# md_ver10_5.net
KiCad netlist of a schematic drawn in EAGLE
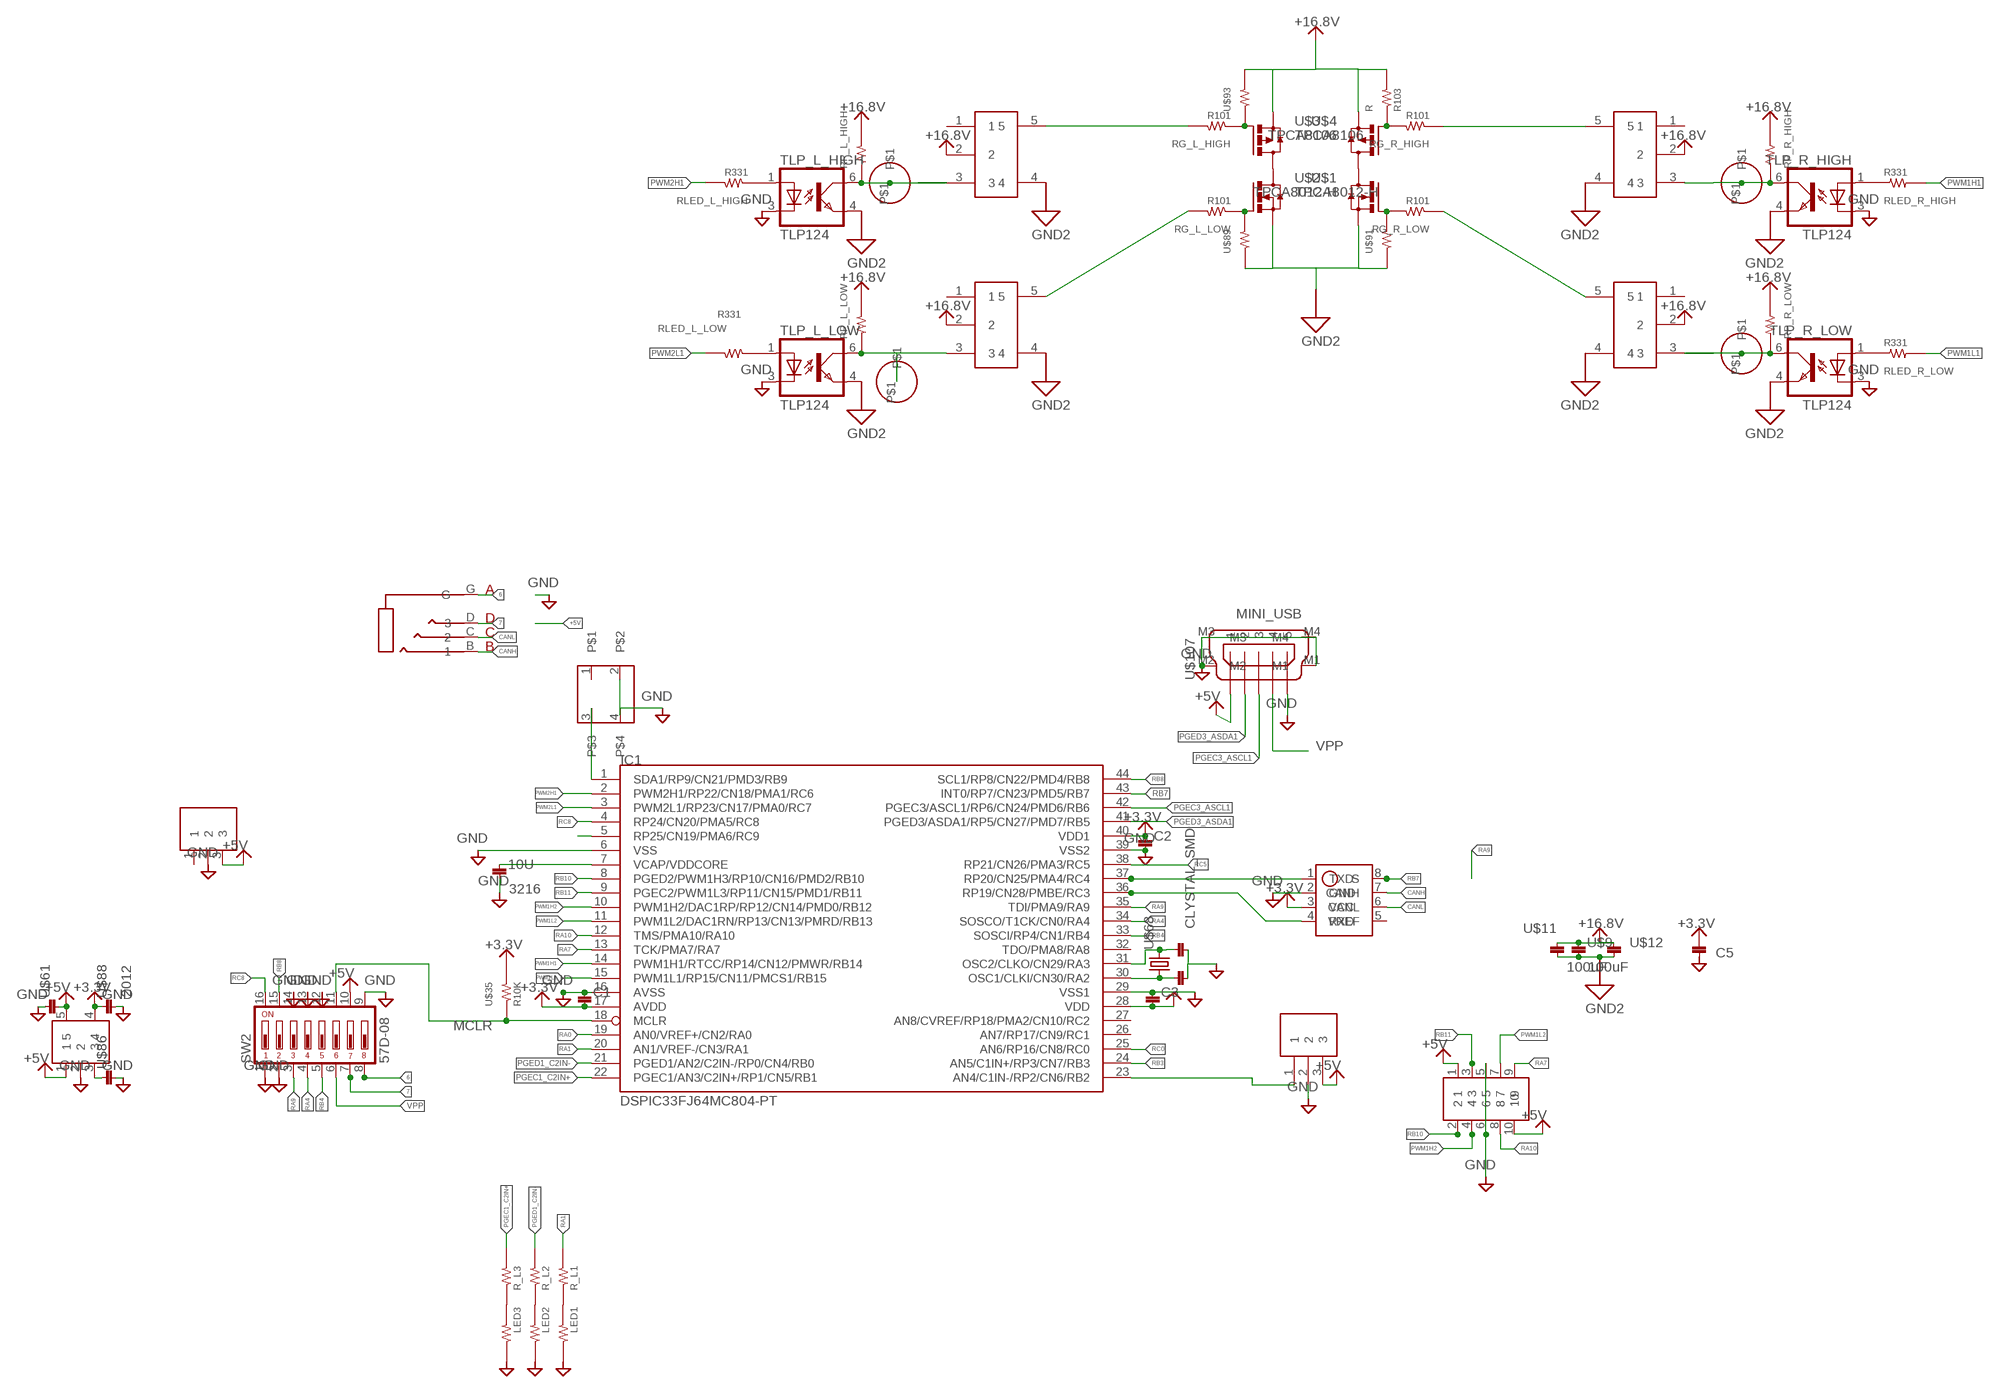
[diagram p0: schematic, sheet 1]

(export (version "E")
  (design (tool "Eeschema 10.0.6"))
  (components
    (comp (ref "10U")
      (value "3216")
      (footprint "eagle-import:3216")
      (libsource (lib "eagle-import") (part "3216"))
    )
    (comp (ref "C")
      (value "C5")
      (footprint "eagle-import:1608")
      (libsource (lib "eagle-import") (part "1608"))
    )
    (comp (ref "C1")
      (value "1608")
      (footprint "eagle-import:1608")
      (libsource (lib "eagle-import") (part "1608"))
    )
    (comp (ref "C2")
      (value "1608")
      (footprint "eagle-import:1608")
      (libsource (lib "eagle-import") (part "1608"))
    )
    (comp (ref "C3")
      (value "1608")
      (footprint "eagle-import:1608")
      (libsource (lib "eagle-import") (part "1608"))
    )
    (comp (ref "IC1")
      (value "DSPIC33FJ64MC804-PT")
      (footprint "eagle-import:TQFP44")
      (libsource (lib "eagle-import") (part "DSPIC33FJ64MC804-PT"))
    )
    (comp (ref "IC2")
      (value "TAR5SB")
      (footprint "eagle-import:SSOP5-P-0.95")
      (libsource (lib "eagle-import") (part "TAR5SB"))
    )
    (comp (ref "IC3")
      (value "ＰＬ－ＩＲＭ")
      (footprint "eagle-import:ＰＬ－ＩＲＭ")
      (libsource (lib "eagle-import") (part "ＰＬ－ＩＲＭ"))
    )
    (comp (ref "IC4")
      (value "SN65HVD1050")
      (footprint "eagle-import:SOIC8")
      (libsource (lib "eagle-import") (part "SN65HVD1050"))
    )
    (comp (ref "IC5")
      (value "Ｒ－７８Ｅ５．０")
      (footprint "eagle-import:Ｒ－７８Ｅ５．０")
      (libsource (lib "eagle-import") (part "Ｒ－７８Ｅ５．０"))
    )
    (comp (ref "IC_L_HIGH")
      (value "MCP1415")
      (footprint "eagle-import:SOT23-5L")
      (libsource (lib "eagle-import") (part "MCP1415"))
    )
    (comp (ref "IC_L_LOW")
      (value "MCP1415")
      (footprint "eagle-import:SOT23-5L")
      (libsource (lib "eagle-import") (part "MCP1415"))
    )
    (comp (ref "IC_R_HIGH")
      (value "MCP1415")
      (footprint "eagle-import:SOT23-5L")
      (libsource (lib "eagle-import") (part "MCP1415"))
    )
    (comp (ref "IC_R_LOW")
      (value "MCP1415")
      (footprint "eagle-import:SOT23-5L")
      (libsource (lib "eagle-import") (part "MCP1415"))
    )
    (comp (ref "R")
      (value "R103")
      (footprint "eagle-import:1608")
      (libsource (lib "eagle-import") (part "RESISTOR__SMD"))
    )
    (comp (ref "RG_L_HIGH")
      (value "R101")
      (footprint "eagle-import:1608")
      (libsource (lib "eagle-import") (part "RESISTOR__SMD"))
    )
    (comp (ref "RG_L_LOW")
      (value "R101")
      (footprint "eagle-import:1608")
      (libsource (lib "eagle-import") (part "RESISTOR__SMD"))
    )
    (comp (ref "RG_R_HIGH")
      (value "R101")
      (footprint "eagle-import:1608")
      (libsource (lib "eagle-import") (part "RESISTOR__SMD"))
    )
    (comp (ref "RG_R_LOW")
      (value "R101")
      (footprint "eagle-import:1608")
      (libsource (lib "eagle-import") (part "RESISTOR__SMD"))
    )
    (comp (ref "RLED_L_HIGH")
      (value "R331")
      (footprint "eagle-import:1608")
      (libsource (lib "eagle-import") (part "RESISTOR__SMD"))
    )
    (comp (ref "RLED_L_LOW")
      (value "R331")
      (footprint "eagle-import:1608")
      (libsource (lib "eagle-import") (part "RESISTOR__SMD"))
    )
    (comp (ref "RLED_R_HIGH")
      (value "R331")
      (footprint "eagle-import:1608")
      (libsource (lib "eagle-import") (part "RESISTOR__SMD"))
    )
    (comp (ref "RLED_R_LOW")
      (value "R331")
      (footprint "eagle-import:1608")
      (libsource (lib "eagle-import") (part "RESISTOR__SMD"))
    )
    (comp (ref "RP_L_HIGH")
      (value "RESISTOR__SMD")
      (footprint "eagle-import:1608")
      (libsource (lib "eagle-import") (part "RESISTOR__SMD"))
    )
    (comp (ref "RP_L_LOW")
      (value "RESISTOR__SMD")
      (footprint "eagle-import:1608")
      (libsource (lib "eagle-import") (part "RESISTOR__SMD"))
    )
    (comp (ref "RP_R_HIGH")
      (value "RESISTOR__SMD")
      (footprint "eagle-import:1608")
      (libsource (lib "eagle-import") (part "RESISTOR__SMD"))
    )
    (comp (ref "RP_R_LOW")
      (value "RESISTOR__SMD")
      (footprint "eagle-import:1608")
      (libsource (lib "eagle-import") (part "RESISTOR__SMD"))
    )
    (comp (ref "SW1")
      (value "TACT")
      (footprint "eagle-import:TL1105")
      (libsource (lib "eagle-import") (part "TACT"))
    )
    (comp (ref "SW2")
      (value "57D-08")
      (footprint "eagle-import:57D")
      (libsource (lib "eagle-import") (part "57D-08"))
    )
    (comp (ref "TLP_L_HIGH")
      (value "TLP124")
      (footprint "eagle-import:11−4C1")
      (libsource (lib "eagle-import") (part "TLP124"))
    )
    (comp (ref "TLP_L_LOW")
      (value "TLP124")
      (footprint "eagle-import:11−4C1")
      (libsource (lib "eagle-import") (part "TLP124"))
    )
    (comp (ref "TLP_R_HIGH")
      (value "TLP124")
      (footprint "eagle-import:11−4C1")
      (libsource (lib "eagle-import") (part "TLP124"))
    )
    (comp (ref "TLP_R_LOW")
      (value "TLP124")
      (footprint "eagle-import:11−4C1")
      (libsource (lib "eagle-import") (part "TLP124"))
    )
    (comp (ref "U$1")
      (value "TPCA8012-H")
      (footprint "eagle-import:2-5Q1A")
      (libsource (lib "eagle-import") (part "TPCA8012-H"))
    )
    (comp (ref "U$2")
      (value "TPCA8012-H")
      (footprint "eagle-import:2-5Q1A")
      (libsource (lib "eagle-import") (part "TPCA8012-H"))
    )
    (comp (ref "U$3")
      (value "TPCA8106")
      (footprint "eagle-import:2-5Q1A")
      (libsource (lib "eagle-import") (part "TPCA8106"))
    )
    (comp (ref "U$4")
      (value "TPCA8106")
      (footprint "eagle-import:2-5Q1A")
      (libsource (lib "eagle-import") (part "TPCA8106"))
    )
    (comp (ref "U$7")
      (value "20pF")
      (footprint "eagle-import:1608")
      (libsource (lib "eagle-import") (part "1608"))
    )
    (comp (ref "U$8")
      (value "20pF")
      (footprint "eagle-import:1608")
      (libsource (lib "eagle-import") (part "1608"))
    )
    (comp (ref "U$9")
      (value "100uF")
      (footprint "eagle-import:3225")
      (libsource (lib "eagle-import") (part "3225"))
    )
    (comp (ref "U$11")
      (value "100uF")
      (footprint "eagle-import:3225")
      (libsource (lib "eagle-import") (part "3225"))
    )
    (comp (ref "U$12")
      (value "3225")
      (footprint "eagle-import:3225")
      (libsource (lib "eagle-import") (part "3225"))
    )
    (comp (ref "U$15")
      (value "PIN_HEADER_52")
      (footprint "eagle-import:PIN_HEADER_5_2")
      (libsource (lib "eagle-import") (part "PIN_HEADER_52"))
    )
    (comp (ref "U$35")
      (value "R10K")
      (footprint "eagle-import:1608")
      (libsource (lib "eagle-import") (part "RESISTOR__SMD"))
    )
    (comp (ref "U$61")
      (value "1608")
      (footprint "eagle-import:1608")
      (libsource (lib "eagle-import") (part "1608"))
    )
    (comp (ref "U$64")
      (value "AUDIO4")
      (footprint "eagle-import:AUDIO4_MJ")
      (libsource (lib "eagle-import") (part "AUDIO4"))
    )
    (comp (ref "U$68")
      (value "CLYSTAL_SMD")
      (footprint "eagle-import:CRYSTAL_SMD")
      (libsource (lib "eagle-import") (part "CLYSTAL_SMD"))
    )
    (comp (ref "U$72")
      (value "R_L3")
      (footprint "eagle-import:1608")
      (libsource (lib "eagle-import") (part "RESISTOR__SMD"))
    )
    (comp (ref "U$74")
      (value "LED3")
      (footprint "eagle-import:1608")
      (libsource (lib "eagle-import") (part "RESISTOR__SMD"))
    )
    (comp (ref "U$75")
      (value "R_L2")
      (footprint "eagle-import:1608")
      (libsource (lib "eagle-import") (part "RESISTOR__SMD"))
    )
    (comp (ref "U$76")
      (value "LED2")
      (footprint "eagle-import:1608")
      (libsource (lib "eagle-import") (part "RESISTOR__SMD"))
    )
    (comp (ref "U$77")
      (value "R_L1")
      (footprint "eagle-import:1608")
      (libsource (lib "eagle-import") (part "RESISTOR__SMD"))
    )
    (comp (ref "U$78")
      (value "LED1")
      (footprint "eagle-import:1608")
      (libsource (lib "eagle-import") (part "RESISTOR__SMD"))
    )
    (comp (ref "U$86")
      (value "1608")
      (footprint "eagle-import:1608")
      (libsource (lib "eagle-import") (part "1608"))
    )
    (comp (ref "U$88")
      (value "2012")
      (footprint "eagle-import:2012")
      (libsource (lib "eagle-import") (part "2012"))
    )
    (comp (ref "U$89")
      (value "RESISTOR__SMD")
      (footprint "eagle-import:1608")
      (libsource (lib "eagle-import") (part "RESISTOR__SMD"))
    )
    (comp (ref "U$91")
      (value "RESISTOR__SMD")
      (footprint "eagle-import:1608")
      (libsource (lib "eagle-import") (part "RESISTOR__SMD"))
    )
    (comp (ref "U$93")
      (value "RESISTOR__SMD")
      (footprint "eagle-import:1608")
      (libsource (lib "eagle-import") (part "RESISTOR__SMD"))
    )
    (comp (ref "U$103")
      (value "PAD1_4MM")
      (footprint "eagle-import:PAD1_4MM")
      (libsource (lib "eagle-import") (part "PAD1_4MM"))
    )
    (comp (ref "U$104")
      (value "PAD1_4MM")
      (footprint "eagle-import:PAD1_4MM")
      (libsource (lib "eagle-import") (part "PAD1_4MM"))
    )
    (comp (ref "U$105")
      (value "PAD1_4MM")
      (footprint "eagle-import:PAD1_4MM")
      (libsource (lib "eagle-import") (part "PAD1_4MM"))
    )
    (comp (ref "U$106")
      (value "PAD1_4MM")
      (footprint "eagle-import:PAD1_4MM")
      (libsource (lib "eagle-import") (part "PAD1_4MM"))
    )
    (comp (ref "U$107")
      (value "MINI_USB")
      (footprint "eagle-import:MINI_USB")
      (libsource (lib "eagle-import") (part "MINI_USB"))
    )
  )
  (nets
    (net (code "1") (name "+3.3V") (class "Default")
      (node (ref "C") (pin "P$1") (pinfunction "1_P$1") (pintype "passive"))
      (node (ref "C1") (pin "P$2") (pinfunction "2_P$2") (pintype "passive"))
      (node (ref "C2") (pin "P$1") (pinfunction "1_P$1") (pintype "passive"))
      (node (ref "C3") (pin "P$2") (pinfunction "2_P$2") (pintype "passive"))
      (node (ref "IC1") (pin "17") (pinfunction "AVDD_17") (pintype "power_in"))
      (node (ref "IC1") (pin "28") (pinfunction "VDD_28") (pintype "power_in"))
      (node (ref "IC1") (pin "40") (pinfunction "VDD1_40") (pintype "power_in"))
      (node (ref "IC2") (pin "4") (pinfunction "4_4") (pintype "bidirectional"))
      (node (ref "IC4") (pin "3") (pinfunction "VCC_3") (pintype "bidirectional"))
      (node (ref "U$35") (pin "2") (pinfunction "P$2_2") (pintype "passive"))
      (node (ref "U$88") (pin "1") (pinfunction "1_1") (pintype "passive"))
    )
    (net (code "2") (name "+5V") (class "Default")
      (node (ref "IC2") (pin "1") (pinfunction "1_1") (pintype "bidirectional"))
      (node (ref "IC2") (pin "5") (pinfunction "5_5") (pintype "bidirectional"))
      (node (ref "IC3") (pin "3") (pinfunction "3_3") (pintype "bidirectional"))
      (node (ref "IC5") (pin "3") (pinfunction "3_3") (pintype "bidirectional"))
      (node (ref "SW2") (pin "10") (pinfunction "10_10") (pintype "passive"))
      (node (ref "U$107") (pin "1") (pinfunction "1_1") (pintype "input"))
      (node (ref "U$15") (pin "1") (pinfunction "1_1") (pintype "bidirectional"))
      (node (ref "U$15") (pin "10") (pinfunction "10_10") (pintype "bidirectional"))
      (node (ref "U$61") (pin "P$2") (pinfunction "2_P$2") (pintype "passive"))
    )
    (net (code "3") (name "+16.8V") (class "Default")
      (node (ref "IC_L_HIGH") (pin "2") (pinfunction "2_2") (pintype "bidirectional"))
      (node (ref "IC_L_LOW") (pin "2") (pinfunction "2_2") (pintype "bidirectional"))
      (node (ref "IC_R_HIGH") (pin "2") (pinfunction "2_2") (pintype "bidirectional"))
      (node (ref "IC_R_LOW") (pin "2") (pinfunction "2_2") (pintype "bidirectional"))
      (node (ref "R") (pin "2") (pinfunction "P$2_2") (pintype "passive"))
      (node (ref "RP_L_HIGH") (pin "2") (pinfunction "P$2_2") (pintype "passive"))
      (node (ref "RP_L_LOW") (pin "2") (pinfunction "P$2_2") (pintype "passive"))
      (node (ref "RP_R_HIGH") (pin "2") (pinfunction "P$2_2") (pintype "passive"))
      (node (ref "RP_R_LOW") (pin "2") (pinfunction "P$2_2") (pintype "passive"))
      (node (ref "U$11") (pin "P$1") (pinfunction "1_P$1") (pintype "passive"))
      (node (ref "U$12") (pin "P$1") (pinfunction "1_P$1") (pintype "passive"))
      (node (ref "U$3") (pin "1") (pinfunction "S_1") (pintype "passive"))
      (node (ref "U$3") (pin "2") (pinfunction "S_2") (pintype "passive"))
      (node (ref "U$3") (pin "3") (pinfunction "S_3") (pintype "passive"))
      (node (ref "U$4") (pin "1") (pinfunction "S_1") (pintype "passive"))
      (node (ref "U$4") (pin "2") (pinfunction "S_2") (pintype "passive"))
      (node (ref "U$4") (pin "3") (pinfunction "S_3") (pintype "passive"))
      (node (ref "U$9") (pin "P$1") (pinfunction "1_P$1") (pintype "passive"))
      (node (ref "U$93") (pin "2") (pinfunction "P$2_2") (pintype "passive"))
    )
    (net (code "4") (name "/MCLR") (class "Default")
      (node (ref "IC1") (pin "18") (pinfunction "MCLR_18") (pintype "input"))
      (node (ref "SW2") (pin "11") (pinfunction "11_11") (pintype "passive"))
      (node (ref "U$35") (pin "1") (pinfunction "P$1_1") (pintype "passive"))
    )
    (net (code "5") (name "6") (class "Default")
      (node (ref "SW2") (pin "8") (pinfunction "8_8") (pintype "passive"))
      (node (ref "U$64") (pin "G") (pinfunction "G_G") (pintype "bidirectional"))
    )
    (net (code "6") (name "7") (class "Default")
      (node (ref "SW2") (pin "7") (pinfunction "7_7") (pintype "passive"))
      (node (ref "U$64") (pin "D") (pinfunction "3_D") (pintype "bidirectional"))
    )
    (net (code "7") (name "CANH") (class "Default")
      (node (ref "IC4") (pin "7") (pinfunction "CANH_7") (pintype "bidirectional"))
      (node (ref "U$64") (pin "B") (pinfunction "1_B") (pintype "bidirectional"))
    )
    (net (code "8") (name "CANL") (class "Default")
      (node (ref "IC4") (pin "6") (pinfunction "CANL_6") (pintype "bidirectional"))
      (node (ref "U$64") (pin "C") (pinfunction "2_C") (pintype "bidirectional"))
    )
    (net (code "9") (name "GND") (class "Default")
      (node (ref "10U") (pin "P$2") (pinfunction "2_P$2") (pintype "passive"))
      (node (ref "C") (pin "P$2") (pinfunction "2_P$2") (pintype "passive"))
      (node (ref "C1") (pin "P$1") (pinfunction "1_P$1") (pintype "passive"))
      (node (ref "C2") (pin "P$2") (pinfunction "2_P$2") (pintype "passive"))
      (node (ref "C3") (pin "P$1") (pinfunction "1_P$1") (pintype "passive"))
      (node (ref "IC1") (pin "16") (pinfunction "AVSS_16") (pintype "power_in"))
      (node (ref "IC1") (pin "29") (pinfunction "VSS1_29") (pintype "power_in"))
      (node (ref "IC1") (pin "39") (pinfunction "VSS2_39") (pintype "power_in"))
      (node (ref "IC1") (pin "6") (pinfunction "VSS_6") (pintype "power_in"))
      (node (ref "IC2") (pin "2") (pinfunction "2_2") (pintype "bidirectional"))
      (node (ref "IC3") (pin "2") (pinfunction "2_2") (pintype "bidirectional"))
      (node (ref "IC4") (pin "2") (pinfunction "GND_2") (pintype "bidirectional"))
      (node (ref "IC5") (pin "2") (pinfunction "2_2") (pintype "bidirectional"))
      (node (ref "SW1") (pin "2") (pinfunction "P$2_2") (pintype "bidirectional"))
      (node (ref "SW1") (pin "4") (pinfunction "P$4_4") (pintype "bidirectional"))
      (node (ref "SW2") (pin "1") (pinfunction "1_1") (pintype "passive"))
      (node (ref "SW2") (pin "12") (pinfunction "12_12") (pintype "passive"))
      (node (ref "SW2") (pin "13") (pinfunction "13_13") (pintype "passive"))
      (node (ref "SW2") (pin "14") (pinfunction "14_14") (pintype "passive"))
      (node (ref "SW2") (pin "2") (pinfunction "2_2") (pintype "passive"))
      (node (ref "SW2") (pin "9") (pinfunction "9_9") (pintype "passive"))
      (node (ref "TLP_L_HIGH") (pin "3") (pinfunction "C_3") (pintype "passive"))
      (node (ref "TLP_L_LOW") (pin "3") (pinfunction "C_3") (pintype "passive"))
      (node (ref "TLP_R_HIGH") (pin "3") (pinfunction "C_3") (pintype "passive"))
      (node (ref "TLP_R_LOW") (pin "3") (pinfunction "C_3") (pintype "passive"))
      (node (ref "U$107") (pin "5") (pinfunction "5_5") (pintype "input"))
      (node (ref "U$107") (pin "M1") (pinfunction "M1_M1") (pintype "bidirectional"))
      (node (ref "U$107") (pin "M2") (pinfunction "M2_M2") (pintype "bidirectional"))
      (node (ref "U$107") (pin "M3") (pinfunction "M3_M3") (pintype "bidirectional"))
      (node (ref "U$107") (pin "M4") (pinfunction "M4_M4") (pintype "bidirectional"))
      (node (ref "U$15") (pin "5") (pinfunction "5_5") (pintype "bidirectional"))
      (node (ref "U$15") (pin "6") (pinfunction "6_6") (pintype "bidirectional"))
      (node (ref "U$61") (pin "P$1") (pinfunction "1_P$1") (pintype "passive"))
      (node (ref "U$7") (pin "P$2") (pinfunction "2_P$2") (pintype "passive"))
      (node (ref "U$74") (pin "1") (pinfunction "P$1_1") (pintype "passive"))
      (node (ref "U$76") (pin "1") (pinfunction "P$1_1") (pintype "passive"))
      (node (ref "U$78") (pin "1") (pinfunction "P$1_1") (pintype "passive"))
      (node (ref "U$8") (pin "P$2") (pinfunction "2_P$2") (pintype "passive"))
      (node (ref "U$86") (pin "P$2") (pinfunction "2_P$2") (pintype "passive"))
      (node (ref "U$88") (pin "2") (pinfunction "2_2") (pintype "passive"))
    )
    (net (code "10") (name "GND2") (class "Default")
      (node (ref "IC_L_HIGH") (pin "4") (pinfunction "4_4") (pintype "bidirectional"))
      (node (ref "IC_L_LOW") (pin "4") (pinfunction "4_4") (pintype "bidirectional"))
      (node (ref "IC_R_HIGH") (pin "4") (pinfunction "4_4") (pintype "bidirectional"))
      (node (ref "IC_R_LOW") (pin "4") (pinfunction "4_4") (pintype "bidirectional"))
      (node (ref "TLP_L_HIGH") (pin "4") (pinfunction "EMIT_4") (pintype "passive"))
      (node (ref "TLP_L_LOW") (pin "4") (pinfunction "EMIT_4") (pintype "passive"))
      (node (ref "TLP_R_HIGH") (pin "4") (pinfunction "EMIT_4") (pintype "passive"))
      (node (ref "TLP_R_LOW") (pin "4") (pinfunction "EMIT_4") (pintype "passive"))
      (node (ref "U$1") (pin "1") (pinfunction "S_1") (pintype "passive"))
      (node (ref "U$1") (pin "2") (pinfunction "S_2") (pintype "passive"))
      (node (ref "U$1") (pin "3") (pinfunction "S_3") (pintype "passive"))
      (node (ref "U$11") (pin "P$2") (pinfunction "2_P$2") (pintype "passive"))
      (node (ref "U$12") (pin "P$2") (pinfunction "2_P$2") (pintype "passive"))
      (node (ref "U$2") (pin "1") (pinfunction "S_1") (pintype "passive"))
      (node (ref "U$2") (pin "2") (pinfunction "S_2") (pintype "passive"))
      (node (ref "U$2") (pin "3") (pinfunction "S_3") (pintype "passive"))
      (node (ref "U$89") (pin "1") (pinfunction "P$1_1") (pintype "passive"))
      (node (ref "U$9") (pin "P$2") (pinfunction "2_P$2") (pintype "passive"))
      (node (ref "U$91") (pin "1") (pinfunction "P$1_1") (pintype "passive"))
    )
    (net (code "11") (name "Net-(10U-1)") (class "Default")
      (node (ref "10U") (pin "P$1") (pinfunction "1_P$1") (pintype "passive"))
      (node (ref "IC1") (pin "7") (pinfunction "VCAP/VDDCORE_7") (pintype "power_in"))
    )
    (net (code "12") (name "Net-(IC1-AN4{slash}C1IN-{slash}RP2{slash}CN6{slash}RB2)") (class "Default")
      (node (ref "IC1") (pin "23") (pinfunction "AN4/C1IN-/RP2/CN6/RB2_23") (pintype "bidirectional"))
      (node (ref "IC3") (pin "1") (pinfunction "1_1") (pintype "bidirectional"))
    )
    (net (code "13") (name "Net-(IC1-OSC1{slash}CLKI{slash}CN30{slash}RA2)") (class "Default")
      (node (ref "IC1") (pin "30") (pinfunction "OSC1/CLKI/CN30/RA2_30") (pintype "bidirectional"))
      (node (ref "U$68") (pin "1") (pinfunction "1_1") (pintype "passive"))
      (node (ref "U$7") (pin "P$1") (pinfunction "1_P$1") (pintype "passive"))
    )
    (net (code "14") (name "Net-(IC1-OSC2{slash}CLKO{slash}CN29{slash}RA3)") (class "Default")
      (node (ref "IC1") (pin "31") (pinfunction "OSC2/CLKO/CN29/RA3_31") (pintype "bidirectional"))
      (node (ref "U$68") (pin "2") (pinfunction "2_2") (pintype "passive"))
      (node (ref "U$8") (pin "P$1") (pinfunction "1_P$1") (pintype "passive"))
    )
    (net (code "15") (name "Net-(IC1-RP19{slash}CN28{slash}PMBE{slash}RC3)") (class "Default")
      (node (ref "IC1") (pin "36") (pinfunction "RP19/CN28/PMBE/RC3_36") (pintype "bidirectional"))
      (node (ref "IC4") (pin "4") (pinfunction "RXD_4") (pintype "bidirectional"))
    )
    (net (code "16") (name "Net-(IC1-RP20{slash}CN25{slash}PMA4{slash}RC4)") (class "Default")
      (node (ref "IC1") (pin "37") (pinfunction "RP20/CN25/PMA4/RC4_37") (pintype "bidirectional"))
      (node (ref "IC4") (pin "1") (pinfunction "TXD_1") (pintype "bidirectional"))
    )
    (net (code "17") (name "Net-(IC1-SDA1{slash}RP9{slash}CN21{slash}PMD3{slash}RB9)") (class "Default")
      (node (ref "IC1") (pin "1") (pinfunction "SDA1/RP9/CN21/PMD3/RB9_1") (pintype "bidirectional"))
      (node (ref "SW1") (pin "3") (pinfunction "P$3_3") (pintype "bidirectional"))
    )
    (net (code "18") (name "Net-(R-P$1)") (class "Default")
      (node (ref "R") (pin "1") (pinfunction "P$1_1") (pintype "passive"))
      (node (ref "RG_R_HIGH") (pin "2") (pinfunction "P$2_2") (pintype "passive"))
      (node (ref "U$4") (pin "4") (pinfunction "G_4") (pintype "passive"))
    )
    (net (code "19") (name "Net-(RG_L_HIGH-P$1)") (class "Default")
      (node (ref "RG_L_HIGH") (pin "1") (pinfunction "P$1_1") (pintype "passive"))
      (node (ref "U$3") (pin "4") (pinfunction "G_4") (pintype "passive"))
      (node (ref "U$93") (pin "1") (pinfunction "P$1_1") (pintype "passive"))
    )
    (net (code "20") (name "Net-(RG_L_HIGH-P$2)") (class "Default")
      (node (ref "IC_L_HIGH") (pin "5") (pinfunction "5_5") (pintype "bidirectional"))
      (node (ref "RG_L_HIGH") (pin "2") (pinfunction "P$2_2") (pintype "passive"))
    )
    (net (code "21") (name "Net-(RG_L_LOW-P$1)") (class "Default")
      (node (ref "RG_L_LOW") (pin "1") (pinfunction "P$1_1") (pintype "passive"))
      (node (ref "U$2") (pin "4") (pinfunction "G_4") (pintype "passive"))
      (node (ref "U$89") (pin "2") (pinfunction "P$2_2") (pintype "passive"))
    )
    (net (code "22") (name "Net-(RG_L_LOW-P$2)") (class "Default")
      (node (ref "IC_L_LOW") (pin "5") (pinfunction "5_5") (pintype "bidirectional"))
      (node (ref "RG_L_LOW") (pin "2") (pinfunction "P$2_2") (pintype "passive"))
    )
    (net (code "23") (name "Net-(RG_R_HIGH-P$1)") (class "Default")
      (node (ref "IC_R_HIGH") (pin "5") (pinfunction "5_5") (pintype "bidirectional"))
      (node (ref "RG_R_HIGH") (pin "1") (pinfunction "P$1_1") (pintype "passive"))
    )
    (net (code "24") (name "Net-(RG_R_LOW-P$1)") (class "Default")
      (node (ref "IC_R_LOW") (pin "5") (pinfunction "5_5") (pintype "bidirectional"))
      (node (ref "RG_R_LOW") (pin "1") (pinfunction "P$1_1") (pintype "passive"))
    )
    (net (code "25") (name "Net-(RG_R_LOW-P$2)") (class "Default")
      (node (ref "RG_R_LOW") (pin "2") (pinfunction "P$2_2") (pintype "passive"))
      (node (ref "U$1") (pin "4") (pinfunction "G_4") (pintype "passive"))
      (node (ref "U$91") (pin "2") (pinfunction "P$2_2") (pintype "passive"))
    )
    (net (code "26") (name "Net-(RLED_L_HIGH-P$1)") (class "Default")
      (node (ref "RLED_L_HIGH") (pin "1") (pinfunction "P$1_1") (pintype "passive"))
      (node (ref "TLP_L_HIGH") (pin "1") (pinfunction "A_1") (pintype "passive"))
    )
    (net (code "27") (name "Net-(RLED_L_LOW-P$1)") (class "Default")
      (node (ref "RLED_L_LOW") (pin "1") (pinfunction "P$1_1") (pintype "passive"))
      (node (ref "TLP_L_LOW") (pin "1") (pinfunction "A_1") (pintype "passive"))
    )
    (net (code "28") (name "Net-(RLED_R_HIGH-P$1)") (class "Default")
      (node (ref "RLED_R_HIGH") (pin "1") (pinfunction "P$1_1") (pintype "passive"))
      (node (ref "TLP_R_HIGH") (pin "1") (pinfunction "A_1") (pintype "passive"))
    )
    (net (code "29") (name "Net-(RLED_R_LOW-P$1)") (class "Default")
      (node (ref "RLED_R_LOW") (pin "1") (pinfunction "P$1_1") (pintype "passive"))
      (node (ref "TLP_R_LOW") (pin "1") (pinfunction "A_1") (pintype "passive"))
    )
    (net (code "30") (name "Net-(RP_L_HIGH-P$1)") (class "Default")
      (node (ref "IC_L_HIGH") (pin "3") (pinfunction "3_3") (pintype "bidirectional"))
      (node (ref "RP_L_HIGH") (pin "1") (pinfunction "P$1_1") (pintype "passive"))
      (node (ref "TLP_L_HIGH") (pin "6") (pinfunction "COL_6") (pintype "passive"))
      (node (ref "U$103") (pin "P$1") (pinfunction "P$1_P$1") (pintype "bidirectional"))
    )
    (net (code "31") (name "Net-(RP_L_LOW-P$1)") (class "Default")
      (node (ref "IC_L_LOW") (pin "3") (pinfunction "3_3") (pintype "bidirectional"))
      (node (ref "RP_L_LOW") (pin "1") (pinfunction "P$1_1") (pintype "passive"))
      (node (ref "TLP_L_LOW") (pin "6") (pinfunction "COL_6") (pintype "passive"))
      (node (ref "U$104") (pin "P$1") (pinfunction "P$1_P$1") (pintype "bidirectional"))
    )
    (net (code "32") (name "Net-(RP_R_HIGH-P$1)") (class "Default")
      (node (ref "IC_R_HIGH") (pin "3") (pinfunction "3_3") (pintype "bidirectional"))
      (node (ref "RP_R_HIGH") (pin "1") (pinfunction "P$1_1") (pintype "passive"))
      (node (ref "TLP_R_HIGH") (pin "6") (pinfunction "COL_6") (pintype "passive"))
      (node (ref "U$105") (pin "P$1") (pinfunction "P$1_P$1") (pintype "bidirectional"))
    )
    (net (code "33") (name "Net-(RP_R_LOW-P$1)") (class "Default")
      (node (ref "IC_R_LOW") (pin "3") (pinfunction "3_3") (pintype "bidirectional"))
      (node (ref "RP_R_LOW") (pin "1") (pinfunction "P$1_1") (pintype "passive"))
      (node (ref "TLP_R_LOW") (pin "6") (pinfunction "COL_6") (pintype "passive"))
      (node (ref "U$106") (pin "P$1") (pinfunction "P$1_P$1") (pintype "bidirectional"))
    )
    (net (code "34") (name "Net-(U$1-D-Pad5)") (class "Default")
      (node (ref "U$1") (pin "5") (pinfunction "D_5") (pintype "passive"))
      (node (ref "U$1") (pin "6") (pinfunction "D_6") (pintype "passive"))
      (node (ref "U$1") (pin "7") (pinfunction "D_7") (pintype "passive"))
      (node (ref "U$1") (pin "8") (pinfunction "D_8") (pintype "passive"))
      (node (ref "U$4") (pin "5") (pinfunction "D_5") (pintype "passive"))
      (node (ref "U$4") (pin "6") (pinfunction "D_6") (pintype "passive"))
      (node (ref "U$4") (pin "7") (pinfunction "D_7") (pintype "passive"))
      (node (ref "U$4") (pin "8") (pinfunction "D_8") (pintype "passive"))
    )
    (net (code "35") (name "Net-(U$2-D-Pad5)") (class "Default")
      (node (ref "U$2") (pin "5") (pinfunction "D_5") (pintype "passive"))
      (node (ref "U$2") (pin "6") (pinfunction "D_6") (pintype "passive"))
      (node (ref "U$2") (pin "7") (pinfunction "D_7") (pintype "passive"))
      (node (ref "U$2") (pin "8") (pinfunction "D_8") (pintype "passive"))
      (node (ref "U$3") (pin "5") (pinfunction "D_5") (pintype "passive"))
      (node (ref "U$3") (pin "6") (pinfunction "D_6") (pintype "passive"))
      (node (ref "U$3") (pin "7") (pinfunction "D_7") (pintype "passive"))
      (node (ref "U$3") (pin "8") (pinfunction "D_8") (pintype "passive"))
    )
    (net (code "36") (name "Net-(U$72-P$1)") (class "Default")
      (node (ref "U$72") (pin "1") (pinfunction "P$1_1") (pintype "passive"))
      (node (ref "U$74") (pin "2") (pinfunction "P$2_2") (pintype "passive"))
    )
    (net (code "37") (name "Net-(U$75-P$1)") (class "Default")
      (node (ref "U$75") (pin "1") (pinfunction "P$1_1") (pintype "passive"))
      (node (ref "U$76") (pin "2") (pinfunction "P$2_2") (pintype "passive"))
    )
    (net (code "38") (name "Net-(U$77-P$1)") (class "Default")
      (node (ref "U$77") (pin "1") (pinfunction "P$1_1") (pintype "passive"))
      (node (ref "U$78") (pin "2") (pinfunction "P$2_2") (pintype "passive"))
    )
    (net (code "39") (name "Net-(U$86-1)") (class "Default")
      (node (ref "IC2") (pin "3") (pinfunction "3_3") (pintype "bidirectional"))
      (node (ref "U$86") (pin "P$1") (pinfunction "1_P$1") (pintype "passive"))
    )
    (net (code "40") (name "PGEC1_C2IN+") (class "Default")
      (node (ref "IC1") (pin "22") (pinfunction "PGEC1/AN3/C2IN+/RP1/CN5/RB1_22") (pintype "bidirectional"))
      (node (ref "U$72") (pin "2") (pinfunction "P$2_2") (pintype "passive"))
    )
    (net (code "41") (name "PGEC3_ASCL1") (class "Default")
      (node (ref "IC1") (pin "42") (pinfunction "PGEC3/ASCL1/RP6/CN24/PMD6/RB6_42") (pintype "bidirectional"))
      (node (ref "U$107") (pin "3") (pinfunction "3_3") (pintype "input"))
    )
    (net (code "42") (name "PGED1_C2IN-") (class "Default")
      (node (ref "IC1") (pin "21") (pinfunction "PGED1/AN2/C2IN-/RP0/CN4/RB0_21") (pintype "bidirectional"))
      (node (ref "U$75") (pin "2") (pinfunction "P$2_2") (pintype "passive"))
    )
    (net (code "43") (name "PGED3_ASDA1") (class "Default")
      (node (ref "IC1") (pin "41") (pinfunction "PGED3/ASDA1/RP5/CN27/PMD7/RB5_41") (pintype "bidirectional"))
      (node (ref "U$107") (pin "2") (pinfunction "2_2") (pintype "input"))
    )
    (net (code "44") (name "PWM1H1") (class "Default")
      (node (ref "IC1") (pin "14") (pinfunction "PWM1H1/RTCC/RP14/CN12/PMWR/RB14_14") (pintype "bidirectional"))
      (node (ref "RLED_R_HIGH") (pin "2") (pinfunction "P$2_2") (pintype "passive"))
    )
    (net (code "45") (name "PWM1H2") (class "Default")
      (node (ref "IC1") (pin "10") (pinfunction "PWM1H2/DAC1RP/RP12/CN14/PMD0/RB12_10") (pintype "bidirectional"))
      (node (ref "U$15") (pin "4") (pinfunction "4_4") (pintype "bidirectional"))
    )
    (net (code "46") (name "PWM1L1") (class "Default")
      (node (ref "IC1") (pin "15") (pinfunction "PWM1L1/RP15/CN11/PMCS1/RB15_15") (pintype "bidirectional"))
      (node (ref "RLED_R_LOW") (pin "2") (pinfunction "P$2_2") (pintype "passive"))
    )
    (net (code "47") (name "PWM1L2") (class "Default")
      (node (ref "IC1") (pin "11") (pinfunction "PWM1L2/DAC1RN/RP13/CN13/PMRD/RB13_11") (pintype "bidirectional"))
      (node (ref "U$15") (pin "7") (pinfunction "7_7") (pintype "bidirectional"))
    )
    (net (code "48") (name "PWM2H1") (class "Default")
      (node (ref "IC1") (pin "2") (pinfunction "PWM2H1/RP22/CN18/PMA1/RC6_2") (pintype "bidirectional"))
      (node (ref "RLED_L_HIGH") (pin "2") (pinfunction "P$2_2") (pintype "passive"))
    )
    (net (code "49") (name "PWM2L1") (class "Default")
      (node (ref "IC1") (pin "3") (pinfunction "PWM2L1/RP23/CN17/PMA0/RC7_3") (pintype "bidirectional"))
      (node (ref "RLED_L_LOW") (pin "2") (pinfunction "P$2_2") (pintype "passive"))
    )
    (net (code "50") (name "RA0") (class "Default")
      (node (ref "IC1") (pin "19") (pinfunction "AN0/VREF+/CN2/RA0_19") (pintype "bidirectional"))
    )
    (net (code "51") (name "RA1") (class "Default")
      (node (ref "IC1") (pin "20") (pinfunction "AN1/VREF-/CN3/RA1_20") (pintype "bidirectional"))
      (node (ref "U$77") (pin "2") (pinfunction "P$2_2") (pintype "passive"))
    )
    (net (code "52") (name "RA4") (class "Default")
      (node (ref "IC1") (pin "34") (pinfunction "SOSCO/T1CK/CN0/RA4_34") (pintype "bidirectional"))
      (node (ref "SW2") (pin "4") (pinfunction "4_4") (pintype "passive"))
    )
    (net (code "53") (name "RA7") (class "Default")
      (node (ref "IC1") (pin "13") (pinfunction "TCK/PMA7/RA7_13") (pintype "bidirectional"))
      (node (ref "U$15") (pin "9") (pinfunction "9_9") (pintype "bidirectional"))
    )
    (net (code "54") (name "RA9") (class "Default")
      (node (ref "IC1") (pin "35") (pinfunction "TDI/PMA9/RA9_35") (pintype "bidirectional"))
      (node (ref "SW2") (pin "3") (pinfunction "3_3") (pintype "passive"))
    )
    (net (code "55") (name "RA10") (class "Default")
      (node (ref "IC1") (pin "12") (pinfunction "TMS/PMA10/RA10_12") (pintype "bidirectional"))
      (node (ref "U$15") (pin "8") (pinfunction "8_8") (pintype "bidirectional"))
    )
    (net (code "56") (name "RB3") (class "Default")
      (node (ref "IC1") (pin "24") (pinfunction "AN5/C1IN+/RP3/CN7/RB3_24") (pintype "bidirectional"))
    )
    (net (code "57") (name "RB4") (class "Default")
      (node (ref "IC1") (pin "33") (pinfunction "SOSCI/RP4/CN1/RB4_33") (pintype "bidirectional"))
      (node (ref "SW2") (pin "5") (pinfunction "5_5") (pintype "passive"))
    )
    (net (code "58") (name "RB7") (class "Default")
      (node (ref "IC1") (pin "43") (pinfunction "INT0/RP7/CN23/PMD5/RB7_43") (pintype "bidirectional"))
      (node (ref "IC4") (pin "8") (pinfunction "S_8") (pintype "bidirectional"))
    )
    (net (code "59") (name "RB8") (class "Default")
      (node (ref "IC1") (pin "44") (pinfunction "SCL1/RP8/CN22/PMD4/RB8_44") (pintype "bidirectional"))
      (node (ref "SW2") (pin "15") (pinfunction "15_15") (pintype "passive"))
    )
    (net (code "60") (name "RB10") (class "Default")
      (node (ref "IC1") (pin "8") (pinfunction "PGED2/PWM1H3/RP10/CN16/PMD2/RB10_8") (pintype "bidirectional"))
      (node (ref "U$15") (pin "2") (pinfunction "2_2") (pintype "bidirectional"))
    )
    (net (code "61") (name "RB11") (class "Default")
      (node (ref "IC1") (pin "9") (pinfunction "PGEC2/PWM1L3/RP11/CN15/PMD1/RB11_9") (pintype "bidirectional"))
      (node (ref "U$15") (pin "3") (pinfunction "3_3") (pintype "bidirectional"))
    )
    (net (code "62") (name "RC0") (class "Default")
      (node (ref "IC1") (pin "25") (pinfunction "AN6/RP16/CN8/RC0_25") (pintype "bidirectional"))
    )
    (net (code "63") (name "RC5") (class "Default")
      (node (ref "IC1") (pin "38") (pinfunction "RP21/CN26/PMA3/RC5_38") (pintype "bidirectional"))
    )
    (net (code "64") (name "RC8") (class "Default")
      (node (ref "IC1") (pin "4") (pinfunction "RP24/CN20/PMA5/RC8_4") (pintype "bidirectional"))
      (node (ref "SW2") (pin "16") (pinfunction "16_16") (pintype "passive"))
    )
    (net (code "65") (name "VPP") (class "Default")
      (node (ref "SW2") (pin "6") (pinfunction "6_6") (pintype "passive"))
      (node (ref "U$107") (pin "4") (pinfunction "4_4") (pintype "input"))
    )
    (net (code "66") (name "unconnected-(IC1-AN7{slash}RP17{slash}CN9{slash}RC1-Pad26)") (class "Default")
      (node (ref "IC1") (pin "26") (pinfunction "AN7/RP17/CN9/RC1_26") (pintype "bidirectional"))
    )
    (net (code "67") (name "unconnected-(IC1-AN8{slash}CVREF{slash}RP18{slash}PMA2{slash}CN10{slash}RC2-Pad27)") (class "Default")
      (node (ref "IC1") (pin "27") (pinfunction "AN8/CVREF/RP18/PMA2/CN10/RC2_27") (pintype "bidirectional"))
    )
    (net (code "68") (name "unconnected-(IC1-RP25{slash}CN19{slash}PMA6{slash}RC9-Pad5)") (class "Default")
      (node (ref "IC1") (pin "5") (pinfunction "RP25/CN19/PMA6/RC9_5") (pintype "bidirectional"))
    )
    (net (code "69") (name "unconnected-(IC1-TDO{slash}PMA8{slash}RA8-Pad32)") (class "Default")
      (node (ref "IC1") (pin "32") (pinfunction "TDO/PMA8/RA8_32") (pintype "bidirectional"))
    )
    (net (code "70") (name "unconnected-(IC4-VREF-Pad5)") (class "Default")
      (node (ref "IC4") (pin "5") (pinfunction "VREF_5") (pintype "bidirectional"))
    )
    (net (code "71") (name "unconnected-(IC5-Pad1)") (class "Default")
      (node (ref "IC5") (pin "1") (pinfunction "1_1") (pintype "bidirectional"))
    )
    (net (code "72") (name "unconnected-(IC_L_HIGH-Pad1)") (class "Default")
      (node (ref "IC_L_HIGH") (pin "1") (pinfunction "1_1") (pintype "bidirectional"))
    )
    (net (code "73") (name "unconnected-(IC_L_LOW-Pad1)") (class "Default")
      (node (ref "IC_L_LOW") (pin "1") (pinfunction "1_1") (pintype "bidirectional"))
    )
    (net (code "74") (name "unconnected-(IC_R_HIGH-Pad1)") (class "Default")
      (node (ref "IC_R_HIGH") (pin "1") (pinfunction "1_1") (pintype "bidirectional"))
    )
    (net (code "75") (name "unconnected-(IC_R_LOW-Pad1)") (class "Default")
      (node (ref "IC_R_LOW") (pin "1") (pinfunction "1_1") (pintype "bidirectional"))
    )
    (net (code "76") (name "unconnected-(SW1-P$1-Pad1)") (class "Default")
      (node (ref "SW1") (pin "1") (pinfunction "P$1_1") (pintype "bidirectional"))
    )
  )
)
